# FlexSensor_2in2.net
KiCad netlist of a schematic drawn in EAGLE
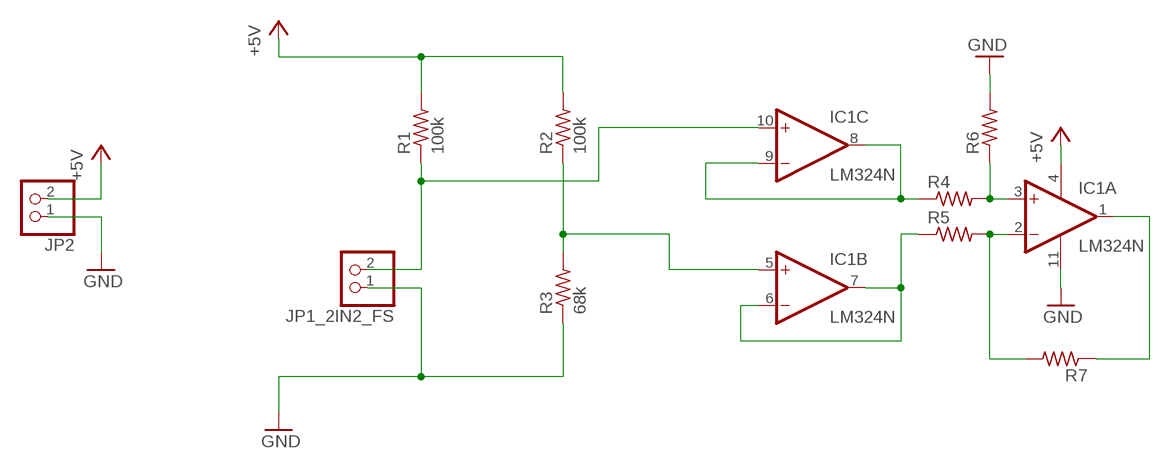
[diagram p0: schematic, sheet 1]

(export (version "E")
  (design (tool "Eeschema 10.0.6"))
  (components
    (comp (ref "IC1")
      (value "LM324N")
      (footprint "eagle-import:DIL14")
      (libsource (lib "eagle-import") (part "LM324N"))
    )
    (comp (ref "JP1_2IN2_FS")
      (value "PINHD-1X2")
      (footprint "eagle-import:1X02")
      (libsource (lib "eagle-import") (part "PINHD-1X2"))
    )
    (comp (ref "JP2")
      (value "PINHD-1X2")
      (footprint "eagle-import:1X02")
      (libsource (lib "eagle-import") (part "PINHD-1X2"))
    )
    (comp (ref "R1")
      (value "100k")
      (footprint "eagle-import:0204_5")
      (libsource (lib "eagle-import") (part "R-US_0204/5"))
    )
    (comp (ref "R2")
      (value "100k")
      (footprint "eagle-import:0204_5")
      (libsource (lib "eagle-import") (part "R-US_0204/5"))
    )
    (comp (ref "R3")
      (value "68k")
      (footprint "eagle-import:0204_5")
      (libsource (lib "eagle-import") (part "R-US_0204/5"))
    )
    (comp (ref "R4")
      (value "R-US_0204/7")
      (footprint "eagle-import:0204_7")
      (libsource (lib "eagle-import") (part "R-US_0204/7"))
    )
    (comp (ref "R5")
      (value "R-US_0204/7")
      (footprint "eagle-import:0204_7")
      (libsource (lib "eagle-import") (part "R-US_0204/7"))
    )
    (comp (ref "R6")
      (value "R-US_0204/7")
      (footprint "eagle-import:0204_7")
      (libsource (lib "eagle-import") (part "R-US_0204/7"))
    )
    (comp (ref "R7")
      (value "R-US_0204/7")
      (footprint "eagle-import:0204_7")
      (libsource (lib "eagle-import") (part "R-US_0204/7"))
    )
  )
  (nets
    (net (code "1") (name "+5V") (class "Default")
      (node (ref "IC1") (pin "4") (pinfunction "V+_4") (pintype "power_in"))
      (node (ref "JP2") (pin "2") (pinfunction "2_2") (pintype "passive"))
      (node (ref "R1") (pin "2") (pinfunction "2_2") (pintype "passive"))
      (node (ref "R2") (pin "2") (pinfunction "2_2") (pintype "passive"))
    )
    (net (code "2") (name "GND") (class "Default")
      (node (ref "IC1") (pin "11") (pinfunction "V-_11") (pintype "power_in"))
      (node (ref "JP1_2IN2_FS") (pin "1") (pinfunction "1_1") (pintype "passive"))
      (node (ref "JP2") (pin "1") (pinfunction "1_1") (pintype "passive"))
      (node (ref "R3") (pin "1") (pinfunction "1_1") (pintype "passive"))
      (node (ref "R6") (pin "2") (pinfunction "2_2") (pintype "passive"))
    )
    (net (code "3") (name "Net-(IC1A-+IN)") (class "Default")
      (node (ref "IC1") (pin "3") (pinfunction "+IN_3") (pintype "input"))
      (node (ref "R4") (pin "2") (pinfunction "2_2") (pintype "passive"))
      (node (ref "R6") (pin "1") (pinfunction "1_1") (pintype "passive"))
    )
    (net (code "4") (name "Net-(IC1A--IN)") (class "Default")
      (node (ref "IC1") (pin "2") (pinfunction "-IN_2") (pintype "input"))
      (node (ref "R5") (pin "2") (pinfunction "2_2") (pintype "passive"))
      (node (ref "R7") (pin "2") (pinfunction "2_2") (pintype "passive"))
    )
    (net (code "5") (name "Net-(IC1A-OUT)") (class "Default")
      (node (ref "IC1") (pin "1") (pinfunction "OUT_1") (pintype "output"))
      (node (ref "R7") (pin "1") (pinfunction "1_1") (pintype "passive"))
    )
    (net (code "6") (name "Net-(IC1B-+IN)") (class "Default")
      (node (ref "IC1") (pin "5") (pinfunction "+IN_5") (pintype "input"))
      (node (ref "R2") (pin "1") (pinfunction "1_1") (pintype "passive"))
      (node (ref "R3") (pin "2") (pinfunction "2_2") (pintype "passive"))
    )
    (net (code "7") (name "Net-(IC1B--IN)") (class "Default")
      (node (ref "IC1") (pin "6") (pinfunction "-IN_6") (pintype "input"))
      (node (ref "IC1") (pin "7") (pinfunction "OUT_7") (pintype "output"))
      (node (ref "R5") (pin "1") (pinfunction "1_1") (pintype "passive"))
    )
    (net (code "8") (name "Net-(IC1C-+IN)") (class "Default")
      (node (ref "IC1") (pin "10") (pinfunction "+IN_10") (pintype "input"))
      (node (ref "JP1_2IN2_FS") (pin "2") (pinfunction "2_2") (pintype "passive"))
      (node (ref "R1") (pin "1") (pinfunction "1_1") (pintype "passive"))
    )
    (net (code "9") (name "Net-(IC1C--IN)") (class "Default")
      (node (ref "IC1") (pin "8") (pinfunction "OUT_8") (pintype "output"))
      (node (ref "IC1") (pin "9") (pinfunction "-IN_9") (pintype "input"))
      (node (ref "R4") (pin "1") (pinfunction "1_1") (pintype "passive"))
    )
  )
)
